# DCDC12180.net
KiCad netlist of a schematic drawn in Altium Designer
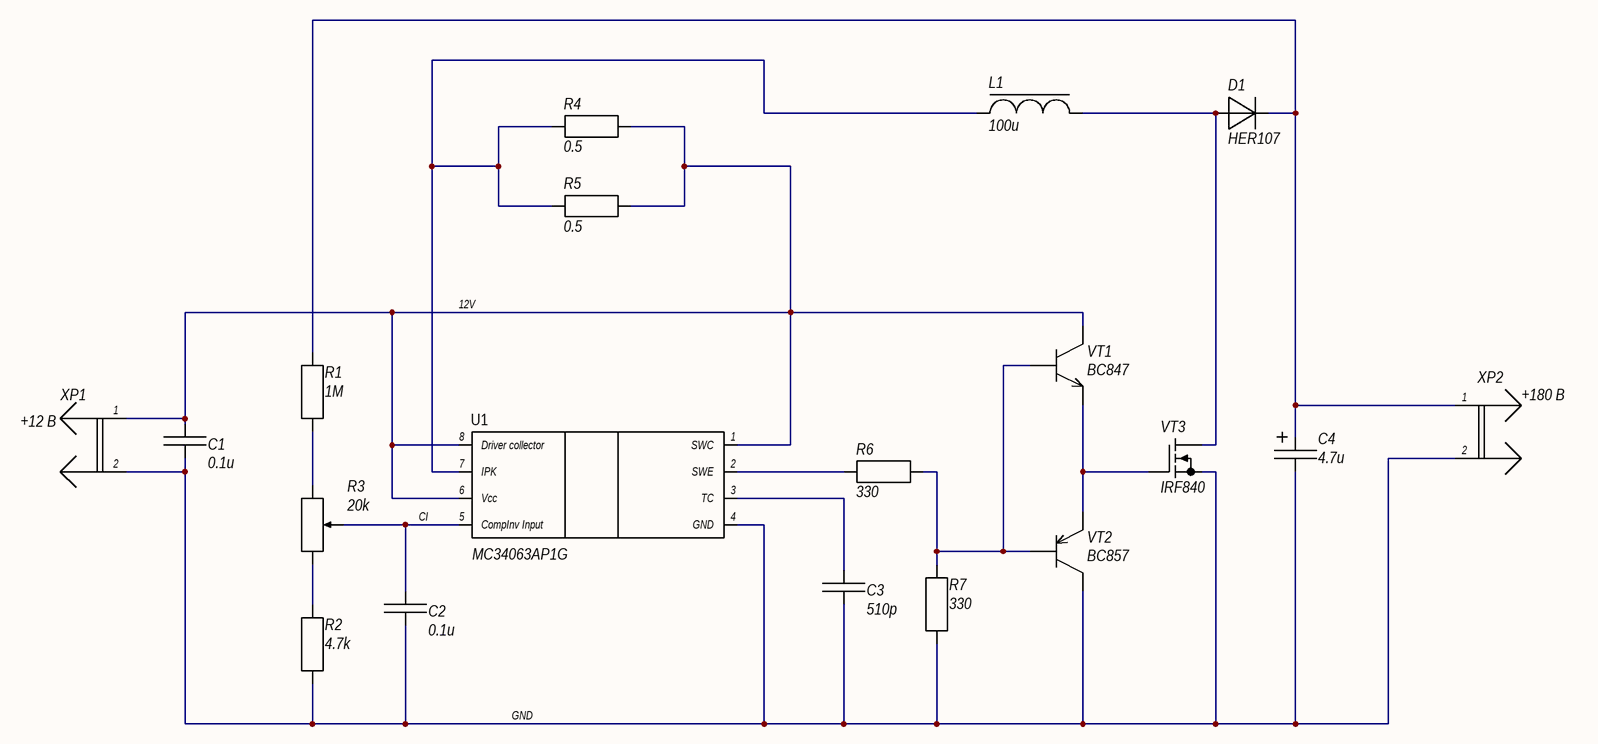
[diagram p0: DCDC12180.SchDoc]

(export (version "E")
  (design (tool "Eeschema 10.0.6"))
  (components
    (comp (ref "C1") (value "0.1u") (footprint "C1206") (libsource (lib "ADolya_Lib") (part "CAPACITOR")))
    (comp (ref "C2") (value "0.1u") (footprint "C1206") (libsource (lib "ADolya_Lib") (part "CAPACITOR")))
    (comp (ref "C3") (value "510p") (footprint "C1206") (libsource (lib "ADolya_Lib") (part "CAPACITOR")))
    (comp (ref "C4")
      (value "4.7u")
      (footprint "ECAP-10x16-5")
      (libsource (lib "ADolya_Lib") (part "CAPACITOR_ECAP"))
    )
    (comp (ref "D1") (value "HER107") (footprint "DO-41") (libsource (lib "ADolya_Lib") (part "DIOD")))
    (comp (ref "L1")
      (value "100u")
      (footprint "INDUCTOR 0912")
      (libsource (lib "ADolya_Lib") (part "INDUCTOR"))
    )
    (comp (ref "R1") (value "1M") (footprint "R1206") (libsource (lib "ADolya_Lib") (part "RESISTOR")))
    (comp (ref "R2") (value "4.7k") (footprint "R1206") (libsource (lib "ADolya_Lib") (part "RESISTOR")))
    (comp (ref "R3")
      (value "20k")
      (footprint "3362P")
      (libsource (lib "ADolya_Lib") (part "RESISTOR-VARIABLE"))
    )
    (comp (ref "R4") (value "0.5") (footprint "R2512") (libsource (lib "ADolya_Lib") (part "RESISTOR")))
    (comp (ref "R5") (value "0.5") (footprint "R2512") (libsource (lib "ADolya_Lib") (part "RESISTOR")))
    (comp (ref "R6") (value "330") (footprint "R1206") (libsource (lib "ADolya_Lib") (part "RESISTOR")))
    (comp (ref "R7") (value "330") (footprint "R1206") (libsource (lib "ADolya_Lib") (part "RESISTOR")))
    (comp (ref "U1")
      (value "MC34063AP1G")
      (footprint "DIP8")
      (libsource (lib "ADolya_Lib") (part "IC-MC34063A"))
    )
    (comp (ref "VT1")
      (value "BC847")
      (footprint "SOT-23")
      (libsource (lib "ADolya_Lib") (part "TRANSISTOR_BC847"))
    )
    (comp (ref "VT2")
      (value "BC857")
      (footprint "SOT-23")
      (libsource (lib "ADolya_Lib") (part "TRANSISTOR_BC857"))
    )
    (comp (ref "VT3")
      (value "IRF840")
      (footprint "TO-220_HORIZONTAL")
      (libsource (lib "ADolya_Lib") (part "IRF840"))
    )
    (comp (ref "XP1")
      (value "+12 В")
      (footprint "2_PIN_INPUT")
      (fields (field (name "PUBLISHER") "Andrew Danich"))
      (libsource (lib "ADolya_Lib") (part "Con-2-M"))
    )
    (comp (ref "XP2")
      (value "+180 В")
      (footprint "2_PIN_INPUT")
      (fields (field (name "PUBLISHER") "Andrew Danich"))
      (libsource (lib "ADolya_Lib") (part "Con-2-M"))
    )
  )
  (nets
    (net (code "1") (name "/12V") (class "Default")
      (node (ref "C1") (pin "2") (pintype "power_in"))
      (node (ref "R4") (pin "2") (pintype "passive"))
      (node (ref "R5") (pin "2") (pintype "passive"))
      (node (ref "U1") (pin "1") (pinfunction "SWC_1") (pintype "power_in"))
      (node (ref "U1") (pin "6") (pinfunction "Vcc_6") (pintype "power_in"))
      (node (ref "U1") (pin "8") (pinfunction "Driver_collector_8") (pintype "power_in"))
      (node (ref "VT1") (pin "3") (pinfunction "К_3") (pintype "passive"))
      (node (ref "XP1") (pin "1") (pintype "passive"))
    )
    (net (code "2") (name "/CI") (class "Default")
      (node (ref "C2") (pin "2") (pintype "power_in"))
      (node (ref "R3") (pin "2") (pinfunction "TAP_2") (pintype "passive"))
      (node (ref "U1") (pin "5") (pinfunction "CompInv_Input_5") (pintype "power_in"))
    )
    (net (code "3") (name "/GND") (class "Default")
      (node (ref "C1") (pin "1") (pintype "power_in"))
      (node (ref "C2") (pin "1") (pintype "power_in"))
      (node (ref "C3") (pin "1") (pintype "power_in"))
      (node (ref "C4") (pin "2") (pintype "power_in"))
      (node (ref "R2") (pin "1") (pintype "passive"))
      (node (ref "R7") (pin "1") (pintype "passive"))
      (node (ref "U1") (pin "4") (pinfunction "GND_4") (pintype "power_in"))
      (node (ref "VT2") (pin "3") (pinfunction "К_3") (pintype "passive"))
      (node (ref "VT3") (pin "3") (pinfunction "S_3") (pintype "passive"))
      (node (ref "XP1") (pin "2") (pintype "passive"))
      (node (ref "XP2") (pin "2") (pintype "passive"))
    )
    (net (code "4") (name "Net-(C4-Pad1)") (class "Default")
      (node (ref "C4") (pin "1") (pintype "power_in"))
      (node (ref "D1") (pin "C") (pintype "power_in"))
      (node (ref "R1") (pin "2") (pintype "passive"))
      (node (ref "XP2") (pin "1") (pintype "passive"))
    )
    (net (code "5") (name "Net-(R1-Pad1)") (class "Default")
      (node (ref "R1") (pin "1") (pintype "passive"))
      (node (ref "R3") (pin "1") (pintype "passive"))
    )
    (net (code "6") (name "Net-(R2-Pad2)") (class "Default")
      (node (ref "R2") (pin "2") (pintype "passive"))
      (node (ref "R3") (pin "3") (pintype "passive"))
    )
    (net (code "7") (name "Net-(U1-IPK)") (class "Default")
      (node (ref "L1") (pin "1") (pinfunction "1_1") (pintype "passive"))
      (node (ref "R4") (pin "1") (pintype "passive"))
      (node (ref "R5") (pin "1") (pintype "passive"))
      (node (ref "U1") (pin "7") (pinfunction "IPK_7") (pintype "power_in"))
    )
    (net (code "8") (name "Net-(U1-SWE)") (class "Default")
      (node (ref "R6") (pin "2") (pintype "passive"))
      (node (ref "U1") (pin "2") (pinfunction "SWE_2") (pintype "power_in"))
    )
    (net (code "9") (name "Net-(U1-TC)") (class "Default")
      (node (ref "C3") (pin "2") (pintype "power_in"))
      (node (ref "U1") (pin "3") (pinfunction "TC_3") (pintype "power_in"))
    )
    (net (code "10") (name "Net-(VT1-Б)") (class "Default")
      (node (ref "R6") (pin "1") (pintype "passive"))
      (node (ref "R7") (pin "2") (pintype "passive"))
      (node (ref "VT1") (pin "1") (pinfunction "Б_1") (pintype "passive"))
      (node (ref "VT2") (pin "1") (pinfunction "Б_1") (pintype "passive"))
    )
    (net (code "11") (name "Net-(VT1-Э)") (class "Default")
      (node (ref "VT1") (pin "2") (pinfunction "Э_2") (pintype "passive"))
      (node (ref "VT2") (pin "2") (pinfunction "Э_2") (pintype "passive"))
      (node (ref "VT3") (pin "1") (pinfunction "G_1") (pintype "passive"))
    )
    (net (code "12") (name "Net-(VT3-D)") (class "Default")
      (node (ref "D1") (pin "A") (pintype "power_in"))
      (node (ref "L1") (pin "2") (pinfunction "2_2") (pintype "passive"))
      (node (ref "VT3") (pin "2") (pinfunction "D_2") (pintype "passive"))
    )
  )
)
